# SensorArray.net
KiCad netlist of a schematic drawn in Altium Designer
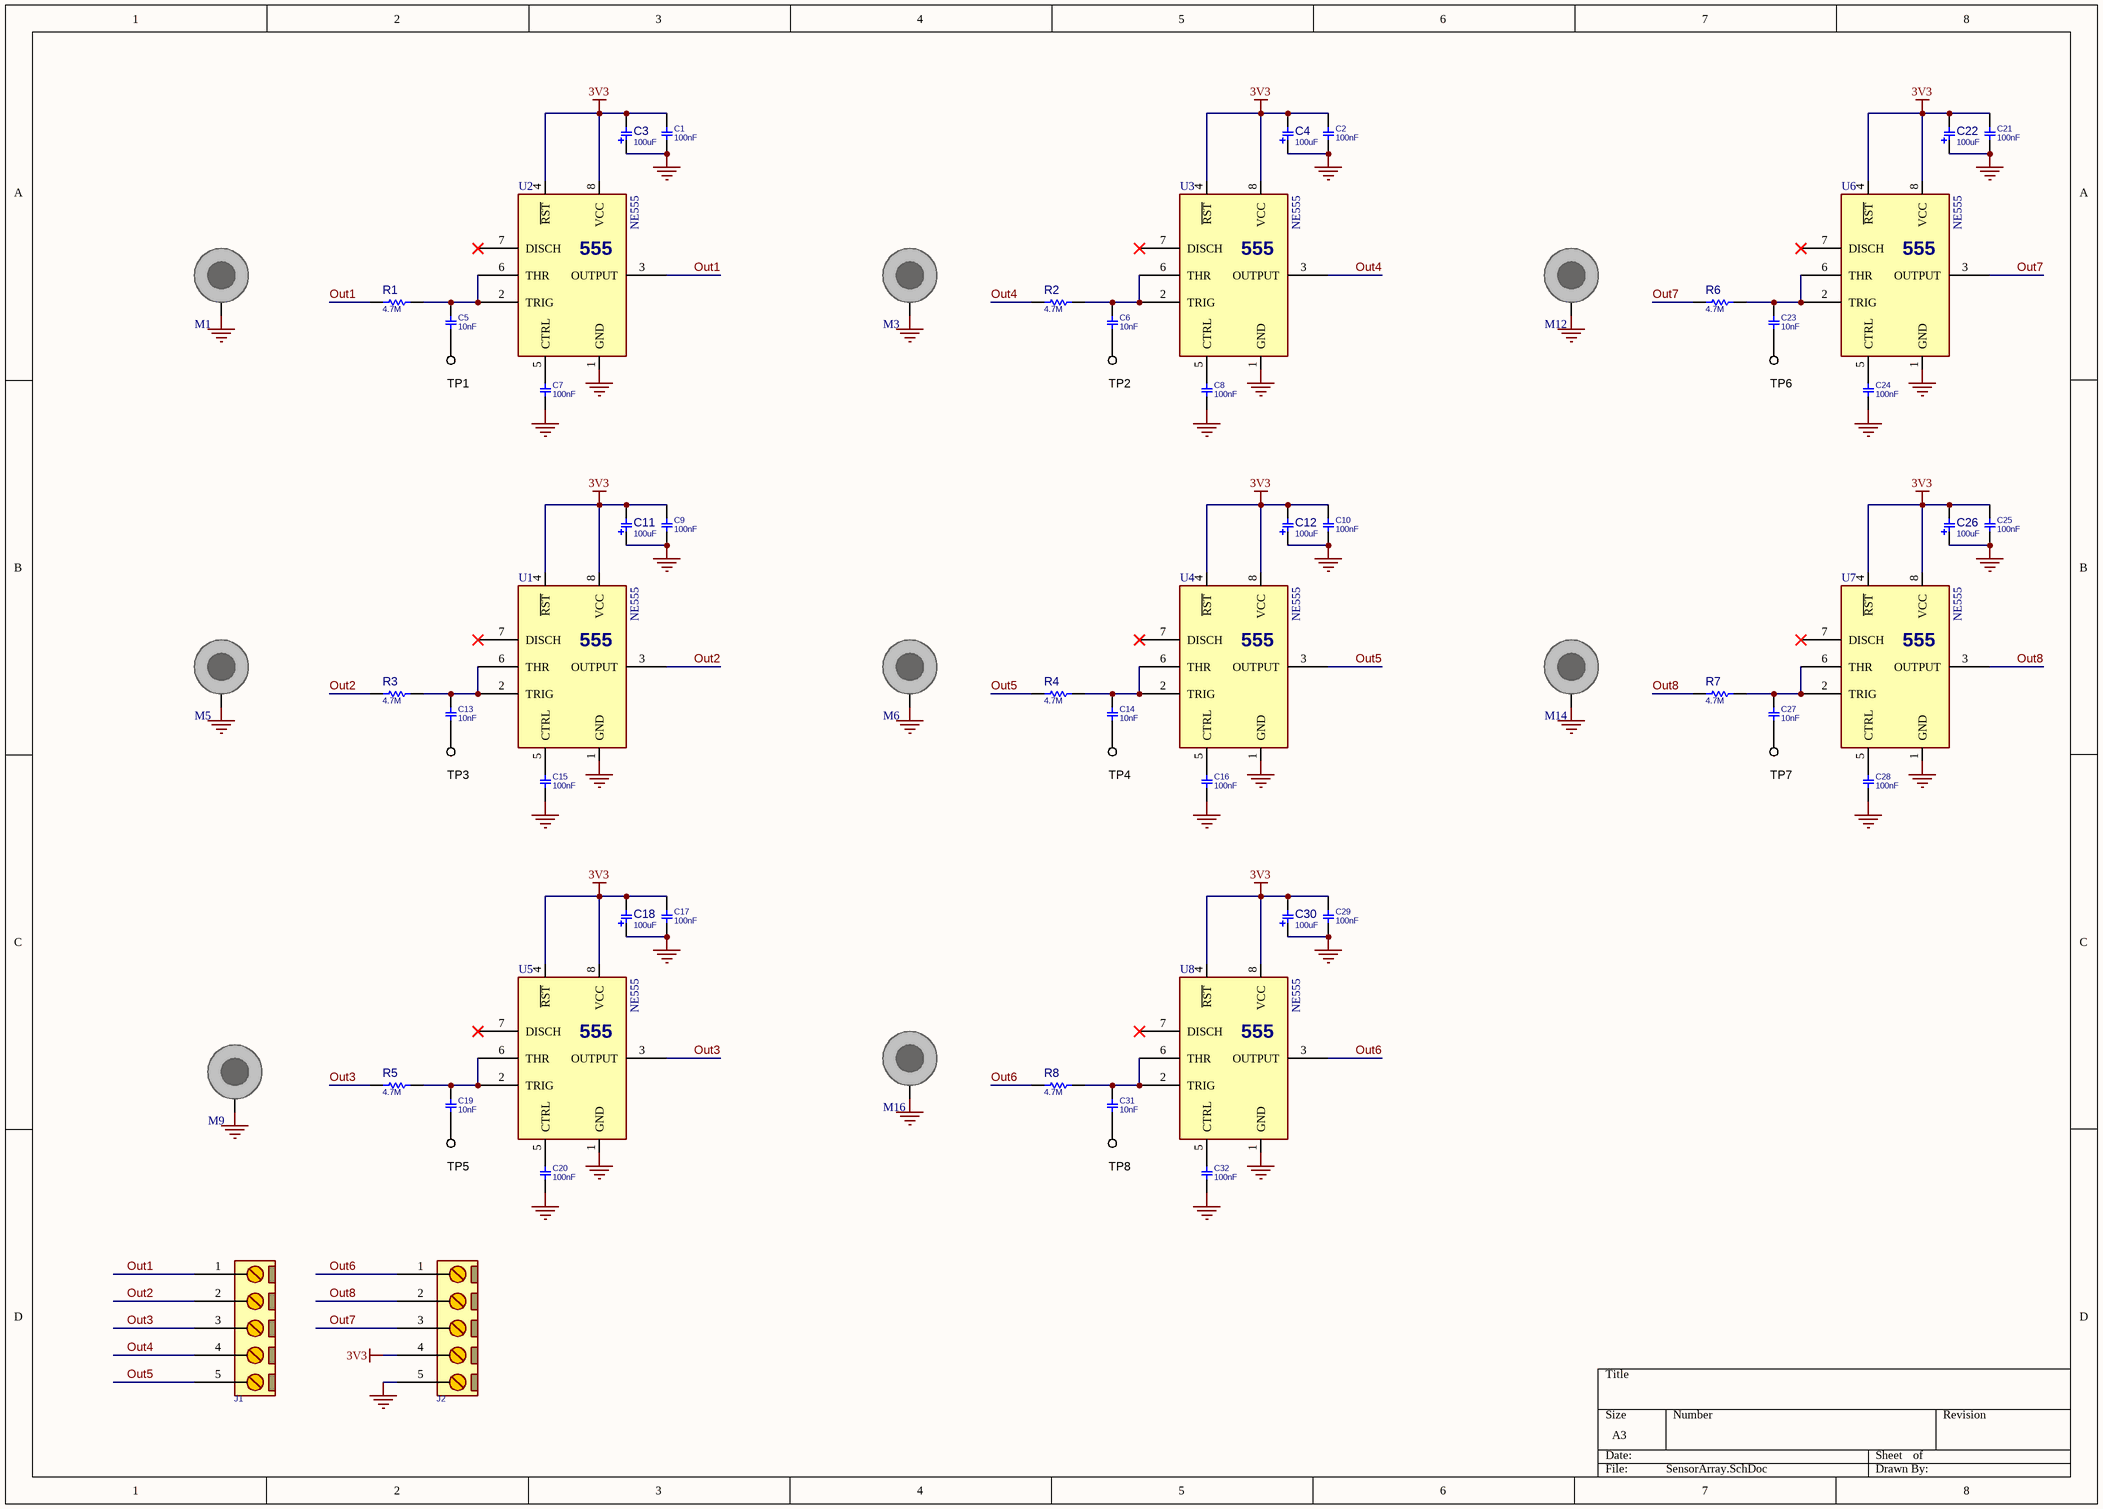
[diagram p0: SensorArray.SchDoc]

(export (version "E")
  (design (tool "Eeschema 10.0.6"))
  (components
    (comp (ref "C1")
      (value "100nF")
      (footprint "C0805")
      (description "CAP, MLCC, -F, -V, MATERIAL, -%, 0201")
      (fields (field (name "MANF_P#") "MANF_PART#"))
      (libsource (lib "passive_smd") (part "CAP_SMD_MLCC_0805"))
    )
    (comp (ref "C2")
      (value "100nF")
      (footprint "C0805")
      (description "CAP, MLCC, -F, -V, MATERIAL, -%, 0201")
      (fields (field (name "MANF_P#") "MANF_PART#"))
      (libsource (lib "passive_smd") (part "CAP_SMD_MLCC_0805"))
    )
    (comp (ref "C3")
      (value "100uF")
      (footprint "C_EL_5")
      (description "CAP, THD, ELEC,")
      (fields (field (name "MANF_P#") "MANF_PART#") (field (name "MANF") "MANF"))
      (libsource (lib "passive_smd") (part "CAP_SMD_EL"))
    )
    (comp (ref "C4")
      (value "100uF")
      (footprint "C_EL_5")
      (description "CAP, THD, ELEC,")
      (fields (field (name "MANF_P#") "MANF_PART#") (field (name "MANF") "MANF"))
      (libsource (lib "passive_smd") (part "CAP_SMD_EL"))
    )
    (comp (ref "C5")
      (value "10nF")
      (footprint "C0805")
      (description "CAP, MLCC, -F, -V, MATERIAL, -%, 0201")
      (fields (field (name "MANF_P#") "MANF_PART#"))
      (libsource (lib "passive_smd") (part "CAP_SMD_MLCC_0805"))
    )
    (comp (ref "C6")
      (value "10nF")
      (footprint "C0805")
      (description "CAP, MLCC, -F, -V, MATERIAL, -%, 0201")
      (fields (field (name "MANF_P#") "MANF_PART#"))
      (libsource (lib "passive_smd") (part "CAP_SMD_MLCC_0805"))
    )
    (comp (ref "C7")
      (value "100nF")
      (footprint "C0805")
      (description "CAP, MLCC, -F, -V, MATERIAL, -%, 0201")
      (fields (field (name "MANF_P#") "MANF_PART#"))
      (libsource (lib "passive_smd") (part "CAP_SMD_MLCC_0805"))
    )
    (comp (ref "C8")
      (value "100nF")
      (footprint "C0805")
      (description "CAP, MLCC, -F, -V, MATERIAL, -%, 0201")
      (fields (field (name "MANF_P#") "MANF_PART#"))
      (libsource (lib "passive_smd") (part "CAP_SMD_MLCC_0805"))
    )
    (comp (ref "C9")
      (value "100nF")
      (footprint "C0805")
      (description "CAP, MLCC, -F, -V, MATERIAL, -%, 0201")
      (fields (field (name "MANF_P#") "MANF_PART#"))
      (libsource (lib "passive_smd") (part "CAP_SMD_MLCC_0805"))
    )
    (comp (ref "C10")
      (value "100nF")
      (footprint "C0805")
      (description "CAP, MLCC, -F, -V, MATERIAL, -%, 0201")
      (fields (field (name "MANF_P#") "MANF_PART#"))
      (libsource (lib "passive_smd") (part "CAP_SMD_MLCC_0805"))
    )
    (comp (ref "C11")
      (value "100uF")
      (footprint "C_EL_5")
      (description "CAP, THD, ELEC,")
      (fields (field (name "MANF_P#") "MANF_PART#") (field (name "MANF") "MANF"))
      (libsource (lib "passive_smd") (part "CAP_SMD_EL"))
    )
    (comp (ref "C12")
      (value "100uF")
      (footprint "C_EL_5")
      (description "CAP, THD, ELEC,")
      (fields (field (name "MANF_P#") "MANF_PART#") (field (name "MANF") "MANF"))
      (libsource (lib "passive_smd") (part "CAP_SMD_EL"))
    )
    (comp (ref "C13")
      (value "10nF")
      (footprint "C0805")
      (description "CAP, MLCC, -F, -V, MATERIAL, -%, 0201")
      (fields (field (name "MANF_P#") "MANF_PART#"))
      (libsource (lib "passive_smd") (part "CAP_SMD_MLCC_0805"))
    )
    (comp (ref "C14")
      (value "10nF")
      (footprint "C0805")
      (description "CAP, MLCC, -F, -V, MATERIAL, -%, 0201")
      (fields (field (name "MANF_P#") "MANF_PART#"))
      (libsource (lib "passive_smd") (part "CAP_SMD_MLCC_0805"))
    )
    (comp (ref "C15")
      (value "100nF")
      (footprint "C0805")
      (description "CAP, MLCC, -F, -V, MATERIAL, -%, 0201")
      (fields (field (name "MANF_P#") "MANF_PART#"))
      (libsource (lib "passive_smd") (part "CAP_SMD_MLCC_0805"))
    )
    (comp (ref "C16")
      (value "100nF")
      (footprint "C0805")
      (description "CAP, MLCC, -F, -V, MATERIAL, -%, 0201")
      (fields (field (name "MANF_P#") "MANF_PART#"))
      (libsource (lib "passive_smd") (part "CAP_SMD_MLCC_0805"))
    )
    (comp (ref "C17")
      (value "100nF")
      (footprint "C0805")
      (description "CAP, MLCC, -F, -V, MATERIAL, -%, 0201")
      (fields (field (name "MANF_P#") "MANF_PART#"))
      (libsource (lib "passive_smd") (part "CAP_SMD_MLCC_0805"))
    )
    (comp (ref "C18")
      (value "100uF")
      (footprint "C_EL_5")
      (description "CAP, THD, ELEC,")
      (fields (field (name "MANF_P#") "MANF_PART#") (field (name "MANF") "MANF"))
      (libsource (lib "passive_smd") (part "CAP_SMD_EL"))
    )
    (comp (ref "C19")
      (value "10nF")
      (footprint "C0805")
      (description "CAP, MLCC, -F, -V, MATERIAL, -%, 0201")
      (fields (field (name "MANF_P#") "MANF_PART#"))
      (libsource (lib "passive_smd") (part "CAP_SMD_MLCC_0805"))
    )
    (comp (ref "C20")
      (value "100nF")
      (footprint "C0805")
      (description "CAP, MLCC, -F, -V, MATERIAL, -%, 0201")
      (fields (field (name "MANF_P#") "MANF_PART#"))
      (libsource (lib "passive_smd") (part "CAP_SMD_MLCC_0805"))
    )
    (comp (ref "C21")
      (value "100nF")
      (footprint "C0805")
      (description "CAP, MLCC, -F, -V, MATERIAL, -%, 0201")
      (fields (field (name "MANF_P#") "MANF_PART#"))
      (libsource (lib "passive_smd") (part "CAP_SMD_MLCC_0805"))
    )
    (comp (ref "C22")
      (value "100uF")
      (footprint "C_EL_5")
      (description "CAP, THD, ELEC,")
      (fields (field (name "MANF_P#") "MANF_PART#") (field (name "MANF") "MANF"))
      (libsource (lib "passive_smd") (part "CAP_SMD_EL"))
    )
    (comp (ref "C23")
      (value "10nF")
      (footprint "C0805")
      (description "CAP, MLCC, -F, -V, MATERIAL, -%, 0201")
      (fields (field (name "MANF_P#") "MANF_PART#"))
      (libsource (lib "passive_smd") (part "CAP_SMD_MLCC_0805"))
    )
    (comp (ref "C24")
      (value "100nF")
      (footprint "C0805")
      (description "CAP, MLCC, -F, -V, MATERIAL, -%, 0201")
      (fields (field (name "MANF_P#") "MANF_PART#"))
      (libsource (lib "passive_smd") (part "CAP_SMD_MLCC_0805"))
    )
    (comp (ref "C25")
      (value "100nF")
      (footprint "C0805")
      (description "CAP, MLCC, -F, -V, MATERIAL, -%, 0201")
      (fields (field (name "MANF_P#") "MANF_PART#"))
      (libsource (lib "passive_smd") (part "CAP_SMD_MLCC_0805"))
    )
    (comp (ref "C26")
      (value "100uF")
      (footprint "C_EL_5")
      (description "CAP, THD, ELEC,")
      (fields (field (name "MANF_P#") "MANF_PART#") (field (name "MANF") "MANF"))
      (libsource (lib "passive_smd") (part "CAP_SMD_EL"))
    )
    (comp (ref "C27")
      (value "10nF")
      (footprint "C0805")
      (description "CAP, MLCC, -F, -V, MATERIAL, -%, 0201")
      (fields (field (name "MANF_P#") "MANF_PART#"))
      (libsource (lib "passive_smd") (part "CAP_SMD_MLCC_0805"))
    )
    (comp (ref "C28")
      (value "100nF")
      (footprint "C0805")
      (description "CAP, MLCC, -F, -V, MATERIAL, -%, 0201")
      (fields (field (name "MANF_P#") "MANF_PART#"))
      (libsource (lib "passive_smd") (part "CAP_SMD_MLCC_0805"))
    )
    (comp (ref "C29")
      (value "100nF")
      (footprint "C0805")
      (description "CAP, MLCC, -F, -V, MATERIAL, -%, 0201")
      (fields (field (name "MANF_P#") "MANF_PART#"))
      (libsource (lib "passive_smd") (part "CAP_SMD_MLCC_0805"))
    )
    (comp (ref "C30")
      (value "100uF")
      (footprint "C_EL_5")
      (description "CAP, THD, ELEC,")
      (fields (field (name "MANF_P#") "MANF_PART#") (field (name "MANF") "MANF"))
      (libsource (lib "passive_smd") (part "CAP_SMD_EL"))
    )
    (comp (ref "C31")
      (value "10nF")
      (footprint "C0805")
      (description "CAP, MLCC, -F, -V, MATERIAL, -%, 0201")
      (fields (field (name "MANF_P#") "MANF_PART#"))
      (libsource (lib "passive_smd") (part "CAP_SMD_MLCC_0805"))
    )
    (comp (ref "C32")
      (value "100nF")
      (footprint "C0805")
      (description "CAP, MLCC, -F, -V, MATERIAL, -%, 0201")
      (fields (field (name "MANF_P#") "MANF_PART#"))
      (libsource (lib "passive_smd") (part "CAP_SMD_MLCC_0805"))
    )
    (comp (ref "J1")
      (value "CONN_TB5")
      (footprint "TBG_5")
      (description "CONN, TERMINAL BLOCK, 5.08mm pitch")
      (libsource (lib "conn_power_terminalB") (part "CONN_TB5"))
    )
    (comp (ref "J2")
      (value "CONN_TB5")
      (footprint "TBG_5")
      (description "CONN, TERMINAL BLOCK, 5.08mm pitch")
      (libsource (lib "conn_power_terminalB") (part "CONN_TB5"))
    )
    (comp (ref "M1")
      (value "DNP/MH")
      (footprint "SCMH_M3")
      (description "SCREW mouting, M3, 3.0mm diameter and 6.0mm PanHead")
      (libsource (lib "mech_mountingHole") (part "SCMH_M3"))
    )
    (comp (ref "M3")
      (value "DNP/MH")
      (footprint "SCMH_M3")
      (description "SCREW mouting, M3, 3.0mm diameter and 6.0mm PanHead")
      (libsource (lib "mech_mountingHole") (part "SCMH_M3"))
    )
    (comp (ref "M5")
      (value "DNP/MH")
      (footprint "SCMH_M3")
      (description "SCREW mouting, M3, 3.0mm diameter and 6.0mm PanHead")
      (libsource (lib "mech_mountingHole") (part "SCMH_M3"))
    )
    (comp (ref "M6")
      (value "DNP/MH")
      (footprint "SCMH_M3")
      (description "SCREW mouting, M3, 3.0mm diameter and 6.0mm PanHead")
      (libsource (lib "mech_mountingHole") (part "SCMH_M3"))
    )
    (comp (ref "M9")
      (value "DNP/MH")
      (footprint "SCMH_M3")
      (description "SCREW mouting, M3, 3.0mm diameter and 6.0mm PanHead")
      (libsource (lib "mech_mountingHole") (part "SCMH_M3"))
    )
    (comp (ref "M12")
      (value "DNP/MH")
      (footprint "SCMH_M3")
      (description "SCREW mouting, M3, 3.0mm diameter and 6.0mm PanHead")
      (libsource (lib "mech_mountingHole") (part "SCMH_M3"))
    )
    (comp (ref "M14")
      (value "DNP/MH")
      (footprint "SCMH_M3")
      (description "SCREW mouting, M3, 3.0mm diameter and 6.0mm PanHead")
      (libsource (lib "mech_mountingHole") (part "SCMH_M3"))
    )
    (comp (ref "M16")
      (value "DNP/MH")
      (footprint "SCMH_M3")
      (description "SCREW mouting, M3, 3.0mm diameter and 6.0mm PanHead")
      (libsource (lib "mech_mountingHole") (part "SCMH_M3"))
    )
    (comp (ref "R1")
      (value "4.7M")
      (footprint "R0805")
      (description "RESISTOR, SMD")
      (libsource (lib "passive_smd") (part "RES_SMD"))
    )
    (comp (ref "R2")
      (value "4.7M")
      (footprint "R0805")
      (description "RESISTOR, SMD")
      (libsource (lib "passive_smd") (part "RES_SMD"))
    )
    (comp (ref "R3")
      (value "4.7M")
      (footprint "R0805")
      (description "RESISTOR, SMD")
      (libsource (lib "passive_smd") (part "RES_SMD"))
    )
    (comp (ref "R4")
      (value "4.7M")
      (footprint "R0805")
      (description "RESISTOR, SMD")
      (libsource (lib "passive_smd") (part "RES_SMD"))
    )
    (comp (ref "R5")
      (value "4.7M")
      (footprint "R0805")
      (description "RESISTOR, SMD")
      (libsource (lib "passive_smd") (part "RES_SMD"))
    )
    (comp (ref "R6")
      (value "4.7M")
      (footprint "R0805")
      (description "RESISTOR, SMD")
      (libsource (lib "passive_smd") (part "RES_SMD"))
    )
    (comp (ref "R7")
      (value "4.7M")
      (footprint "R0805")
      (description "RESISTOR, SMD")
      (libsource (lib "passive_smd") (part "RES_SMD"))
    )
    (comp (ref "R8")
      (value "4.7M")
      (footprint "R0805")
      (description "RESISTOR, SMD")
      (libsource (lib "passive_smd") (part "RES_SMD"))
    )
    (comp (ref "TP1")
      (value "TESTPOINT_SMD")
      (footprint "TPSMD_S1")
      (description "TEST POINT")
      (fields (field (name "MANF") "MANF") (field (name "MANF_P#") "MANF_P#"))
      (libsource (lib "test-tp_jumper") (part "TESTPOINT_SMD"))
    )
    (comp (ref "TP2")
      (value "TESTPOINT_SMD")
      (footprint "TPSMD_S1")
      (description "TEST POINT")
      (fields (field (name "MANF") "MANF") (field (name "MANF_P#") "MANF_P#"))
      (libsource (lib "test-tp_jumper") (part "TESTPOINT_SMD"))
    )
    (comp (ref "TP3")
      (value "TESTPOINT_SMD")
      (footprint "TPSMD_S1")
      (description "TEST POINT")
      (fields (field (name "MANF") "MANF") (field (name "MANF_P#") "MANF_P#"))
      (libsource (lib "test-tp_jumper") (part "TESTPOINT_SMD"))
    )
    (comp (ref "TP4")
      (value "TESTPOINT_SMD")
      (footprint "TPSMD_S1")
      (description "TEST POINT")
      (fields (field (name "MANF") "MANF") (field (name "MANF_P#") "MANF_P#"))
      (libsource (lib "test-tp_jumper") (part "TESTPOINT_SMD"))
    )
    (comp (ref "TP5")
      (value "TESTPOINT_SMD")
      (footprint "TPSMD_S1")
      (description "TEST POINT")
      (fields (field (name "MANF") "MANF") (field (name "MANF_P#") "MANF_P#"))
      (libsource (lib "test-tp_jumper") (part "TESTPOINT_SMD"))
    )
    (comp (ref "TP6")
      (value "TESTPOINT_SMD")
      (footprint "TPSMD_S1")
      (description "TEST POINT")
      (fields (field (name "MANF") "MANF") (field (name "MANF_P#") "MANF_P#"))
      (libsource (lib "test-tp_jumper") (part "TESTPOINT_SMD"))
    )
    (comp (ref "TP7")
      (value "TESTPOINT_SMD")
      (footprint "TPSMD_S1")
      (description "TEST POINT")
      (fields (field (name "MANF") "MANF") (field (name "MANF_P#") "MANF_P#"))
      (libsource (lib "test-tp_jumper") (part "TESTPOINT_SMD"))
    )
    (comp (ref "TP8")
      (value "TESTPOINT_SMD")
      (footprint "TPSMD_S1")
      (description "TEST POINT")
      (fields (field (name "MANF") "MANF") (field (name "MANF_P#") "MANF_P#"))
      (libsource (lib "test-tp_jumper") (part "TESTPOINT_SMD"))
    )
    (comp (ref "U1")
      (value "NE555")
      (footprint "DIP_8")
      (description "555 Timer, General-Purpose Single Bipolar Timer")
      (fields (field (name "MANF_P#") "NE555DR,") (field (name "MANF") "Texas Instruments"))
      (libsource (lib "ic_timer_555") (part "NE555_SOP8"))
    )
    (comp (ref "U2")
      (value "NE555")
      (footprint "DIP_8")
      (description "555 Timer, General-Purpose Single Bipolar Timer")
      (fields (field (name "MANF_P#") "NE555DR,") (field (name "MANF") "Texas Instruments"))
      (libsource (lib "ic_timer_555") (part "NE555_SOP8"))
    )
    (comp (ref "U3")
      (value "NE555")
      (footprint "DIP_8")
      (description "555 Timer, General-Purpose Single Bipolar Timer")
      (fields (field (name "MANF_P#") "NE555DR,") (field (name "MANF") "Texas Instruments"))
      (libsource (lib "ic_timer_555") (part "NE555_SOP8"))
    )
    (comp (ref "U4")
      (value "NE555")
      (footprint "DIP_8")
      (description "555 Timer, General-Purpose Single Bipolar Timer")
      (fields (field (name "MANF_P#") "NE555DR,") (field (name "MANF") "Texas Instruments"))
      (libsource (lib "ic_timer_555") (part "NE555_SOP8"))
    )
    (comp (ref "U5")
      (value "NE555")
      (footprint "DIP_8")
      (description "555 Timer, General-Purpose Single Bipolar Timer")
      (fields (field (name "MANF_P#") "NE555DR,") (field (name "MANF") "Texas Instruments"))
      (libsource (lib "ic_timer_555") (part "NE555_SOP8"))
    )
    (comp (ref "U6")
      (value "NE555")
      (footprint "DIP_8")
      (description "555 Timer, General-Purpose Single Bipolar Timer")
      (fields (field (name "MANF_P#") "NE555DR,") (field (name "MANF") "Texas Instruments"))
      (libsource (lib "ic_timer_555") (part "NE555_SOP8"))
    )
    (comp (ref "U7")
      (value "NE555")
      (footprint "DIP_8")
      (description "555 Timer, General-Purpose Single Bipolar Timer")
      (fields (field (name "MANF_P#") "NE555DR,") (field (name "MANF") "Texas Instruments"))
      (libsource (lib "ic_timer_555") (part "NE555_SOP8"))
    )
    (comp (ref "U8")
      (value "NE555")
      (footprint "DIP_8")
      (description "555 Timer, General-Purpose Single Bipolar Timer")
      (fields (field (name "MANF_P#") "NE555DR,") (field (name "MANF") "Texas Instruments"))
      (libsource (lib "ic_timer_555") (part "NE555_SOP8"))
    )
  )
  (nets
    (net (code "1") (name "/Out1") (class "Default")
      (node (ref "J1") (pin "1") (pinfunction "1_1") (pintype "passive"))
      (node (ref "R1") (pin "1") (pinfunction "1_1") (pintype "passive"))
      (node (ref "U2") (pin "3") (pinfunction "OUTPUT_3") (pintype "passive"))
    )
    (net (code "2") (name "/Out2") (class "Default")
      (node (ref "J1") (pin "2") (pinfunction "2_2") (pintype "passive"))
      (node (ref "R3") (pin "1") (pinfunction "1_1") (pintype "passive"))
      (node (ref "U1") (pin "3") (pinfunction "OUTPUT_3") (pintype "passive"))
    )
    (net (code "3") (name "/Out3") (class "Default")
      (node (ref "J1") (pin "3") (pinfunction "3_3") (pintype "passive"))
      (node (ref "R5") (pin "1") (pinfunction "1_1") (pintype "passive"))
      (node (ref "U5") (pin "3") (pinfunction "OUTPUT_3") (pintype "passive"))
    )
    (net (code "4") (name "/Out4") (class "Default")
      (node (ref "J1") (pin "4") (pinfunction "4_4") (pintype "passive"))
      (node (ref "R2") (pin "1") (pinfunction "1_1") (pintype "passive"))
      (node (ref "U3") (pin "3") (pinfunction "OUTPUT_3") (pintype "passive"))
    )
    (net (code "5") (name "/Out5") (class "Default")
      (node (ref "J1") (pin "5") (pinfunction "5_5") (pintype "passive"))
      (node (ref "R4") (pin "1") (pinfunction "1_1") (pintype "passive"))
      (node (ref "U4") (pin "3") (pinfunction "OUTPUT_3") (pintype "passive"))
    )
    (net (code "6") (name "/Out6") (class "Default")
      (node (ref "J2") (pin "1") (pinfunction "1_1") (pintype "passive"))
      (node (ref "R8") (pin "1") (pinfunction "1_1") (pintype "passive"))
      (node (ref "U8") (pin "3") (pinfunction "OUTPUT_3") (pintype "passive"))
    )
    (net (code "7") (name "/Out7") (class "Default")
      (node (ref "J2") (pin "3") (pinfunction "3_3") (pintype "passive"))
      (node (ref "R6") (pin "1") (pinfunction "1_1") (pintype "passive"))
      (node (ref "U6") (pin "3") (pinfunction "OUTPUT_3") (pintype "passive"))
    )
    (net (code "8") (name "/Out8") (class "Default")
      (node (ref "J2") (pin "2") (pinfunction "2_2") (pintype "passive"))
      (node (ref "R7") (pin "1") (pinfunction "1_1") (pintype "passive"))
      (node (ref "U7") (pin "3") (pinfunction "OUTPUT_3") (pintype "passive"))
    )
    (net (code "9") (name "3V3") (class "Default")
      (node (ref "C1") (pin "2") (pinfunction "2_2") (pintype "passive"))
      (node (ref "C10") (pin "2") (pinfunction "2_2") (pintype "passive"))
      (node (ref "C11") (pin "2") (pinfunction "2_2") (pintype "passive"))
      (node (ref "C12") (pin "2") (pinfunction "2_2") (pintype "passive"))
      (node (ref "C17") (pin "2") (pinfunction "2_2") (pintype "passive"))
      (node (ref "C18") (pin "2") (pinfunction "2_2") (pintype "passive"))
      (node (ref "C2") (pin "2") (pinfunction "2_2") (pintype "passive"))
      (node (ref "C21") (pin "2") (pinfunction "2_2") (pintype "passive"))
      (node (ref "C22") (pin "2") (pinfunction "2_2") (pintype "passive"))
      (node (ref "C25") (pin "2") (pinfunction "2_2") (pintype "passive"))
      (node (ref "C26") (pin "2") (pinfunction "2_2") (pintype "passive"))
      (node (ref "C29") (pin "2") (pinfunction "2_2") (pintype "passive"))
      (node (ref "C3") (pin "2") (pinfunction "2_2") (pintype "passive"))
      (node (ref "C30") (pin "2") (pinfunction "2_2") (pintype "passive"))
      (node (ref "C4") (pin "2") (pinfunction "2_2") (pintype "passive"))
      (node (ref "C9") (pin "2") (pinfunction "2_2") (pintype "passive"))
      (node (ref "J2") (pin "4") (pinfunction "4_4") (pintype "passive"))
      (node (ref "U1") (pin "4") (pinfunction "~{RST}_4") (pintype "passive"))
      (node (ref "U1") (pin "8") (pinfunction "VCC_8") (pintype "passive"))
      (node (ref "U2") (pin "4") (pinfunction "~{RST}_4") (pintype "passive"))
      (node (ref "U2") (pin "8") (pinfunction "VCC_8") (pintype "passive"))
      (node (ref "U3") (pin "4") (pinfunction "~{RST}_4") (pintype "passive"))
      (node (ref "U3") (pin "8") (pinfunction "VCC_8") (pintype "passive"))
      (node (ref "U4") (pin "4") (pinfunction "~{RST}_4") (pintype "passive"))
      (node (ref "U4") (pin "8") (pinfunction "VCC_8") (pintype "passive"))
      (node (ref "U5") (pin "4") (pinfunction "~{RST}_4") (pintype "passive"))
      (node (ref "U5") (pin "8") (pinfunction "VCC_8") (pintype "passive"))
      (node (ref "U6") (pin "4") (pinfunction "~{RST}_4") (pintype "passive"))
      (node (ref "U6") (pin "8") (pinfunction "VCC_8") (pintype "passive"))
      (node (ref "U7") (pin "4") (pinfunction "~{RST}_4") (pintype "passive"))
      (node (ref "U7") (pin "8") (pinfunction "VCC_8") (pintype "passive"))
      (node (ref "U8") (pin "4") (pinfunction "~{RST}_4") (pintype "passive"))
      (node (ref "U8") (pin "8") (pinfunction "VCC_8") (pintype "passive"))
    )
    (net (code "10") (name "GND") (class "Default")
      (node (ref "C1") (pin "1") (pinfunction "1_1") (pintype "passive"))
      (node (ref "C10") (pin "1") (pinfunction "1_1") (pintype "passive"))
      (node (ref "C11") (pin "1") (pinfunction "1_1") (pintype "passive"))
      (node (ref "C12") (pin "1") (pinfunction "1_1") (pintype "passive"))
      (node (ref "C15") (pin "1") (pinfunction "1_1") (pintype "passive"))
      (node (ref "C16") (pin "1") (pinfunction "1_1") (pintype "passive"))
      (node (ref "C17") (pin "1") (pinfunction "1_1") (pintype "passive"))
      (node (ref "C18") (pin "1") (pinfunction "1_1") (pintype "passive"))
      (node (ref "C2") (pin "1") (pinfunction "1_1") (pintype "passive"))
      (node (ref "C20") (pin "1") (pinfunction "1_1") (pintype "passive"))
      (node (ref "C21") (pin "1") (pinfunction "1_1") (pintype "passive"))
      (node (ref "C22") (pin "1") (pinfunction "1_1") (pintype "passive"))
      (node (ref "C24") (pin "1") (pinfunction "1_1") (pintype "passive"))
      (node (ref "C25") (pin "1") (pinfunction "1_1") (pintype "passive"))
      (node (ref "C26") (pin "1") (pinfunction "1_1") (pintype "passive"))
      (node (ref "C28") (pin "1") (pinfunction "1_1") (pintype "passive"))
      (node (ref "C29") (pin "1") (pinfunction "1_1") (pintype "passive"))
      (node (ref "C3") (pin "1") (pinfunction "1_1") (pintype "passive"))
      (node (ref "C30") (pin "1") (pinfunction "1_1") (pintype "passive"))
      (node (ref "C32") (pin "1") (pinfunction "1_1") (pintype "passive"))
      (node (ref "C4") (pin "1") (pinfunction "1_1") (pintype "passive"))
      (node (ref "C7") (pin "1") (pinfunction "1_1") (pintype "passive"))
      (node (ref "C8") (pin "1") (pinfunction "1_1") (pintype "passive"))
      (node (ref "C9") (pin "1") (pinfunction "1_1") (pintype "passive"))
      (node (ref "J2") (pin "5") (pinfunction "5_5") (pintype "passive"))
      (node (ref "M1") (pin "1") (pinfunction "1_1") (pintype "passive"))
      (node (ref "M12") (pin "1") (pinfunction "1_1") (pintype "passive"))
      (node (ref "M14") (pin "1") (pinfunction "1_1") (pintype "passive"))
      (node (ref "M16") (pin "1") (pinfunction "1_1") (pintype "passive"))
      (node (ref "M3") (pin "1") (pinfunction "1_1") (pintype "passive"))
      (node (ref "M5") (pin "1") (pinfunction "1_1") (pintype "passive"))
      (node (ref "M6") (pin "1") (pinfunction "1_1") (pintype "passive"))
      (node (ref "M9") (pin "1") (pinfunction "1_1") (pintype "passive"))
      (node (ref "U1") (pin "1") (pinfunction "GND_1") (pintype "passive"))
      (node (ref "U2") (pin "1") (pinfunction "GND_1") (pintype "passive"))
      (node (ref "U3") (pin "1") (pinfunction "GND_1") (pintype "passive"))
      (node (ref "U4") (pin "1") (pinfunction "GND_1") (pintype "passive"))
      (node (ref "U5") (pin "1") (pinfunction "GND_1") (pintype "passive"))
      (node (ref "U6") (pin "1") (pinfunction "GND_1") (pintype "passive"))
      (node (ref "U7") (pin "1") (pinfunction "GND_1") (pintype "passive"))
      (node (ref "U8") (pin "1") (pinfunction "GND_1") (pintype "passive"))
    )
    (net (code "11") (name "Net-(C5-Pad1)") (class "Default")
      (node (ref "C5") (pin "1") (pinfunction "1_1") (pintype "passive"))
      (node (ref "TP1") (pin "1") (pinfunction "1_1") (pintype "passive"))
    )
    (net (code "12") (name "Net-(C6-Pad1)") (class "Default")
      (node (ref "C6") (pin "1") (pinfunction "1_1") (pintype "passive"))
      (node (ref "TP2") (pin "1") (pinfunction "1_1") (pintype "passive"))
    )
    (net (code "13") (name "Net-(C13-Pad1)") (class "Default")
      (node (ref "C13") (pin "1") (pinfunction "1_1") (pintype "passive"))
      (node (ref "TP3") (pin "1") (pinfunction "1_1") (pintype "passive"))
    )
    (net (code "14") (name "Net-(C14-Pad1)") (class "Default")
      (node (ref "C14") (pin "1") (pinfunction "1_1") (pintype "passive"))
      (node (ref "TP4") (pin "1") (pinfunction "1_1") (pintype "passive"))
    )
    (net (code "15") (name "Net-(C19-Pad1)") (class "Default")
      (node (ref "C19") (pin "1") (pinfunction "1_1") (pintype "passive"))
      (node (ref "TP5") (pin "1") (pinfunction "1_1") (pintype "passive"))
    )
    (net (code "16") (name "Net-(C23-Pad1)") (class "Default")
      (node (ref "C23") (pin "1") (pinfunction "1_1") (pintype "passive"))
      (node (ref "TP6") (pin "1") (pinfunction "1_1") (pintype "passive"))
    )
    (net (code "17") (name "Net-(C27-Pad1)") (class "Default")
      (node (ref "C27") (pin "1") (pinfunction "1_1") (pintype "passive"))
      (node (ref "TP7") (pin "1") (pinfunction "1_1") (pintype "passive"))
    )
    (net (code "18") (name "Net-(C31-Pad1)") (class "Default")
      (node (ref "C31") (pin "1") (pinfunction "1_1") (pintype "passive"))
      (node (ref "TP8") (pin "1") (pinfunction "1_1") (pintype "passive"))
    )
    (net (code "19") (name "Net-(U1-CTRL)") (class "Default")
      (node (ref "C15") (pin "2") (pinfunction "2_2") (pintype "passive"))
      (node (ref "U1") (pin "5") (pinfunction "CTRL_5") (pintype "passive"))
    )
    (net (code "20") (name "Net-(U1-THR)") (class "Default")
      (node (ref "C13") (pin "2") (pinfunction "2_2") (pintype "passive"))
      (node (ref "R3") (pin "2") (pinfunction "2_2") (pintype "passive"))
      (node (ref "U1") (pin "2") (pinfunction "TRIG_2") (pintype "passive"))
      (node (ref "U1") (pin "6") (pinfunction "THR_6") (pintype "passive"))
    )
    (net (code "21") (name "Net-(U2-CTRL)") (class "Default")
      (node (ref "C7") (pin "2") (pinfunction "2_2") (pintype "passive"))
      (node (ref "U2") (pin "5") (pinfunction "CTRL_5") (pintype "passive"))
    )
    (net (code "22") (name "Net-(U2-THR)") (class "Default")
      (node (ref "C5") (pin "2") (pinfunction "2_2") (pintype "passive"))
      (node (ref "R1") (pin "2") (pinfunction "2_2") (pintype "passive"))
      (node (ref "U2") (pin "2") (pinfunction "TRIG_2") (pintype "passive"))
      (node (ref "U2") (pin "6") (pinfunction "THR_6") (pintype "passive"))
    )
    (net (code "23") (name "Net-(U3-CTRL)") (class "Default")
      (node (ref "C8") (pin "2") (pinfunction "2_2") (pintype "passive"))
      (node (ref "U3") (pin "5") (pinfunction "CTRL_5") (pintype "passive"))
    )
    (net (code "24") (name "Net-(U3-THR)") (class "Default")
      (node (ref "C6") (pin "2") (pinfunction "2_2") (pintype "passive"))
      (node (ref "R2") (pin "2") (pinfunction "2_2") (pintype "passive"))
      (node (ref "U3") (pin "2") (pinfunction "TRIG_2") (pintype "passive"))
      (node (ref "U3") (pin "6") (pinfunction "THR_6") (pintype "passive"))
    )
    (net (code "25") (name "Net-(U4-CTRL)") (class "Default")
      (node (ref "C16") (pin "2") (pinfunction "2_2") (pintype "passive"))
      (node (ref "U4") (pin "5") (pinfunction "CTRL_5") (pintype "passive"))
    )
    (net (code "26") (name "Net-(U4-THR)") (class "Default")
      (node (ref "C14") (pin "2") (pinfunction "2_2") (pintype "passive"))
      (node (ref "R4") (pin "2") (pinfunction "2_2") (pintype "passive"))
      (node (ref "U4") (pin "2") (pinfunction "TRIG_2") (pintype "passive"))
      (node (ref "U4") (pin "6") (pinfunction "THR_6") (pintype "passive"))
    )
    (net (code "27") (name "Net-(U5-CTRL)") (class "Default")
      (node (ref "C20") (pin "2") (pinfunction "2_2") (pintype "passive"))
      (node (ref "U5") (pin "5") (pinfunction "CTRL_5") (pintype "passive"))
    )
    (net (code "28") (name "Net-(U5-THR)") (class "Default")
      (node (ref "C19") (pin "2") (pinfunction "2_2") (pintype "passive"))
      (node (ref "R5") (pin "2") (pinfunction "2_2") (pintype "passive"))
      (node (ref "U5") (pin "2") (pinfunction "TRIG_2") (pintype "passive"))
      (node (ref "U5") (pin "6") (pinfunction "THR_6") (pintype "passive"))
    )
    (net (code "29") (name "Net-(U6-CTRL)") (class "Default")
      (node (ref "C24") (pin "2") (pinfunction "2_2") (pintype "passive"))
      (node (ref "U6") (pin "5") (pinfunction "CTRL_5") (pintype "passive"))
    )
    (net (code "30") (name "Net-(U6-THR)") (class "Default")
      (node (ref "C23") (pin "2") (pinfunction "2_2") (pintype "passive"))
      (node (ref "R6") (pin "2") (pinfunction "2_2") (pintype "passive"))
      (node (ref "U6") (pin "2") (pinfunction "TRIG_2") (pintype "passive"))
      (node (ref "U6") (pin "6") (pinfunction "THR_6") (pintype "passive"))
    )
    (net (code "31") (name "Net-(U7-CTRL)") (class "Default")
      (node (ref "C28") (pin "2") (pinfunction "2_2") (pintype "passive"))
      (node (ref "U7") (pin "5") (pinfunction "CTRL_5") (pintype "passive"))
    )
    (net (code "32") (name "Net-(U7-THR)") (class "Default")
      (node (ref "C27") (pin "2") (pinfunction "2_2") (pintype "passive"))
      (node (ref "R7") (pin "2") (pinfunction "2_2") (pintype "passive"))
      (node (ref "U7") (pin "2") (pinfunction "TRIG_2") (pintype "passive"))
      (node (ref "U7") (pin "6") (pinfunction "THR_6") (pintype "passive"))
    )
    (net (code "33") (name "Net-(U8-CTRL)") (class "Default")
      (node (ref "C32") (pin "2") (pinfunction "2_2") (pintype "passive"))
      (node (ref "U8") (pin "5") (pinfunction "CTRL_5") (pintype "passive"))
    )
    (net (code "34") (name "Net-(U8-THR)") (class "Default")
      (node (ref "C31") (pin "2") (pinfunction "2_2") (pintype "passive"))
      (node (ref "R8") (pin "2") (pinfunction "2_2") (pintype "passive"))
      (node (ref "U8") (pin "2") (pinfunction "TRIG_2") (pintype "passive"))
      (node (ref "U8") (pin "6") (pinfunction "THR_6") (pintype "passive"))
    )
    (net (code "35") (name "unconnected-(U1-DISCH-Pad7)") (class "Default")
      (node (ref "U1") (pin "7") (pinfunction "DISCH_7") (pintype "passive+no_connect"))
    )
    (net (code "36") (name "unconnected-(U2-DISCH-Pad7)") (class "Default")
      (node (ref "U2") (pin "7") (pinfunction "DISCH_7") (pintype "passive+no_connect"))
    )
    (net (code "37") (name "unconnected-(U3-DISCH-Pad7)") (class "Default")
      (node (ref "U3") (pin "7") (pinfunction "DISCH_7") (pintype "passive+no_connect"))
    )
    (net (code "38") (name "unconnected-(U4-DISCH-Pad7)") (class "Default")
      (node (ref "U4") (pin "7") (pinfunction "DISCH_7") (pintype "passive+no_connect"))
    )
    (net (code "39") (name "unconnected-(U5-DISCH-Pad7)") (class "Default")
      (node (ref "U5") (pin "7") (pinfunction "DISCH_7") (pintype "passive+no_connect"))
    )
    (net (code "40") (name "unconnected-(U6-DISCH-Pad7)") (class "Default")
      (node (ref "U6") (pin "7") (pinfunction "DISCH_7") (pintype "passive+no_connect"))
    )
    (net (code "41") (name "unconnected-(U7-DISCH-Pad7)") (class "Default")
      (node (ref "U7") (pin "7") (pinfunction "DISCH_7") (pintype "passive+no_connect"))
    )
    (net (code "42") (name "unconnected-(U8-DISCH-Pad7)") (class "Default")
      (node (ref "U8") (pin "7") (pinfunction "DISCH_7") (pintype "passive+no_connect"))
    )
  )
)
